# riffle-proto-grove-1_2.net
KiCad netlist of a schematic drawn in EAGLE
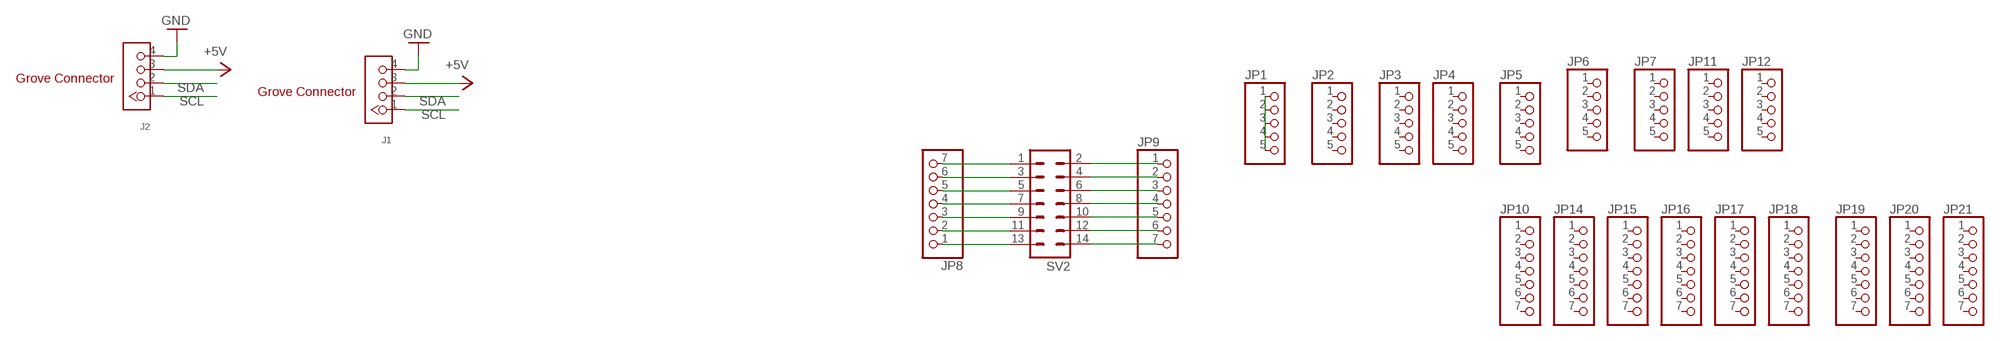
[diagram p0: schematic, sheet 1]

(export (version "E")
  (design (tool "Eeschema 10.0.6"))
  (components
    (comp (ref "J1")
      (value "TWIG-4P-2.0-2.0")
      (footprint "eagle-import:4P-2.0")
      (libsource (lib "eagle-import") (part "TWIG-4P-2.0-2.0"))
    )
    (comp (ref "J2")
      (value "TWIG-4P-2.0-2.0")
      (footprint "eagle-import:4P-2.0")
      (libsource (lib "eagle-import") (part "TWIG-4P-2.0-2.0"))
    )
    (comp (ref "JP1")
      (value "HEADER-1X570MIL")
      (footprint "eagle-import:1X05_ROUND_70")
      (libsource (lib "eagle-import") (part "HEADER-1X570MIL"))
    )
    (comp (ref "JP2")
      (value "HEADER-1X570MIL")
      (footprint "eagle-import:1X05_ROUND_70")
      (libsource (lib "eagle-import") (part "HEADER-1X570MIL"))
    )
    (comp (ref "JP3")
      (value "HEADER-1X570MIL")
      (footprint "eagle-import:1X05_ROUND_70")
      (libsource (lib "eagle-import") (part "HEADER-1X570MIL"))
    )
    (comp (ref "JP4")
      (value "HEADER-1X570MIL")
      (footprint "eagle-import:1X05_ROUND_70")
      (libsource (lib "eagle-import") (part "HEADER-1X570MIL"))
    )
    (comp (ref "JP5")
      (value "HEADER-1X570MIL")
      (footprint "eagle-import:1X05_ROUND_70")
      (libsource (lib "eagle-import") (part "HEADER-1X570MIL"))
    )
    (comp (ref "JP6")
      (value "HEADER-1X570MIL")
      (footprint "eagle-import:1X05_ROUND_70")
      (libsource (lib "eagle-import") (part "HEADER-1X570MIL"))
    )
    (comp (ref "JP7")
      (value "HEADER-1X570MIL")
      (footprint "eagle-import:1X05_ROUND_70")
      (libsource (lib "eagle-import") (part "HEADER-1X570MIL"))
    )
    (comp (ref "JP8")
      (value "HEADER-1X770MIL")
      (footprint "eagle-import:1X07_ROUND_70")
      (libsource (lib "eagle-import") (part "HEADER-1X770MIL"))
    )
    (comp (ref "JP9")
      (value "HEADER-1X770MIL")
      (footprint "eagle-import:1X07_ROUND_70")
      (libsource (lib "eagle-import") (part "HEADER-1X770MIL"))
    )
    (comp (ref "JP10")
      (value "HEADER-1X770MIL")
      (footprint "eagle-import:1X07_ROUND_70")
      (libsource (lib "eagle-import") (part "HEADER-1X770MIL"))
    )
    (comp (ref "JP11")
      (value "HEADER-1X570MIL")
      (footprint "eagle-import:1X05_ROUND_70")
      (libsource (lib "eagle-import") (part "HEADER-1X570MIL"))
    )
    (comp (ref "JP12")
      (value "HEADER-1X570MIL")
      (footprint "eagle-import:1X05_ROUND_70")
      (libsource (lib "eagle-import") (part "HEADER-1X570MIL"))
    )
    (comp (ref "JP14")
      (value "HEADER-1X770MIL")
      (footprint "eagle-import:1X07_ROUND_70")
      (libsource (lib "eagle-import") (part "HEADER-1X770MIL"))
    )
    (comp (ref "JP15")
      (value "HEADER-1X770MIL")
      (footprint "eagle-import:1X07_ROUND_70")
      (libsource (lib "eagle-import") (part "HEADER-1X770MIL"))
    )
    (comp (ref "JP16")
      (value "HEADER-1X770MIL")
      (footprint "eagle-import:1X07_ROUND_70")
      (libsource (lib "eagle-import") (part "HEADER-1X770MIL"))
    )
    (comp (ref "JP17")
      (value "HEADER-1X770MIL")
      (footprint "eagle-import:1X07_ROUND_70")
      (libsource (lib "eagle-import") (part "HEADER-1X770MIL"))
    )
    (comp (ref "JP18")
      (value "HEADER-1X770MIL")
      (footprint "eagle-import:1X07_ROUND_70")
      (libsource (lib "eagle-import") (part "HEADER-1X770MIL"))
    )
    (comp (ref "JP19")
      (value "HEADER-1X770MIL")
      (footprint "eagle-import:1X07_ROUND_70")
      (libsource (lib "eagle-import") (part "HEADER-1X770MIL"))
    )
    (comp (ref "JP20")
      (value "HEADER-1X770MIL")
      (footprint "eagle-import:1X07_ROUND_70")
      (libsource (lib "eagle-import") (part "HEADER-1X770MIL"))
    )
    (comp (ref "JP21")
      (value "HEADER-1X770MIL")
      (footprint "eagle-import:1X07_ROUND_70")
      (libsource (lib "eagle-import") (part "HEADER-1X770MIL"))
    )
    (comp (ref "SV2")
      (value "MA07-2")
      (footprint "eagle-import:MA07-2")
      (libsource (lib "eagle-import") (part "MA07-2"))
    )
  )
  (nets
    (net (code "1") (name "+5V") (class "Default")
      (node (ref "J1") (pin "3") (pinfunction "3_3") (pintype "bidirectional"))
      (node (ref "J2") (pin "3") (pinfunction "3_3") (pintype "bidirectional"))
    )
    (net (code "2") (name "/SCL") (class "Default")
      (node (ref "J1") (pin "1") (pinfunction "1_1") (pintype "bidirectional"))
      (node (ref "J2") (pin "1") (pinfunction "1_1") (pintype "bidirectional"))
    )
    (net (code "3") (name "/SDA") (class "Default")
      (node (ref "J1") (pin "2") (pinfunction "2_2") (pintype "bidirectional"))
      (node (ref "J2") (pin "2") (pinfunction "2_2") (pintype "bidirectional"))
    )
    (net (code "4") (name "GND") (class "Default")
      (node (ref "J1") (pin "4") (pinfunction "4_4") (pintype "bidirectional"))
      (node (ref "J2") (pin "4") (pinfunction "4_4") (pintype "bidirectional"))
    )
    (net (code "5") (name "Net-(JP1-Pad1)") (class "Default")
      (node (ref "JP1") (pin "1") (pinfunction "1_1") (pintype "passive"))
      (node (ref "JP1") (pin "2") (pinfunction "2_2") (pintype "passive"))
      (node (ref "JP1") (pin "3") (pinfunction "3_3") (pintype "passive"))
      (node (ref "JP1") (pin "4") (pinfunction "4_4") (pintype "passive"))
      (node (ref "JP1") (pin "5") (pinfunction "5_5") (pintype "passive"))
    )
    (net (code "6") (name "Net-(JP8-Pad1)") (class "Default")
      (node (ref "JP8") (pin "1") (pinfunction "1_1") (pintype "passive"))
      (node (ref "SV2") (pin "13") (pinfunction "13_13") (pintype "passive"))
    )
    (net (code "7") (name "Net-(JP8-Pad2)") (class "Default")
      (node (ref "JP8") (pin "2") (pinfunction "2_2") (pintype "passive"))
      (node (ref "SV2") (pin "11") (pinfunction "11_11") (pintype "passive"))
    )
    (net (code "8") (name "Net-(JP8-Pad3)") (class "Default")
      (node (ref "JP8") (pin "3") (pinfunction "3_3") (pintype "passive"))
      (node (ref "SV2") (pin "9") (pinfunction "9_9") (pintype "passive"))
    )
    (net (code "9") (name "Net-(JP8-Pad4)") (class "Default")
      (node (ref "JP8") (pin "4") (pinfunction "4_4") (pintype "passive"))
      (node (ref "SV2") (pin "7") (pinfunction "7_7") (pintype "passive"))
    )
    (net (code "10") (name "Net-(JP8-Pad5)") (class "Default")
      (node (ref "JP8") (pin "5") (pinfunction "5_5") (pintype "passive"))
      (node (ref "SV2") (pin "5") (pinfunction "5_5") (pintype "passive"))
    )
    (net (code "11") (name "Net-(JP8-Pad6)") (class "Default")
      (node (ref "JP8") (pin "6") (pinfunction "6_6") (pintype "passive"))
      (node (ref "SV2") (pin "3") (pinfunction "3_3") (pintype "passive"))
    )
    (net (code "12") (name "Net-(JP8-Pad7)") (class "Default")
      (node (ref "JP8") (pin "7") (pinfunction "7_7") (pintype "passive"))
      (node (ref "SV2") (pin "1") (pinfunction "1_1") (pintype "passive"))
    )
    (net (code "13") (name "Net-(JP9-Pad1)") (class "Default")
      (node (ref "JP9") (pin "1") (pinfunction "1_1") (pintype "passive"))
      (node (ref "SV2") (pin "2") (pinfunction "2_2") (pintype "passive"))
    )
    (net (code "14") (name "Net-(JP9-Pad2)") (class "Default")
      (node (ref "JP9") (pin "2") (pinfunction "2_2") (pintype "passive"))
      (node (ref "SV2") (pin "4") (pinfunction "4_4") (pintype "passive"))
    )
    (net (code "15") (name "Net-(JP9-Pad3)") (class "Default")
      (node (ref "JP9") (pin "3") (pinfunction "3_3") (pintype "passive"))
      (node (ref "SV2") (pin "6") (pinfunction "6_6") (pintype "passive"))
    )
    (net (code "16") (name "Net-(JP9-Pad4)") (class "Default")
      (node (ref "JP9") (pin "4") (pinfunction "4_4") (pintype "passive"))
      (node (ref "SV2") (pin "8") (pinfunction "8_8") (pintype "passive"))
    )
    (net (code "17") (name "Net-(JP9-Pad5)") (class "Default")
      (node (ref "JP9") (pin "5") (pinfunction "5_5") (pintype "passive"))
      (node (ref "SV2") (pin "10") (pinfunction "10_10") (pintype "passive"))
    )
    (net (code "18") (name "Net-(JP9-Pad6)") (class "Default")
      (node (ref "JP9") (pin "6") (pinfunction "6_6") (pintype "passive"))
      (node (ref "SV2") (pin "12") (pinfunction "12_12") (pintype "passive"))
    )
    (net (code "19") (name "Net-(JP9-Pad7)") (class "Default")
      (node (ref "JP9") (pin "7") (pinfunction "7_7") (pintype "passive"))
      (node (ref "SV2") (pin "14") (pinfunction "14_14") (pintype "passive"))
    )
    (net (code "20") (name "unconnected-(JP2-Pad1)") (class "Default")
      (node (ref "JP2") (pin "1") (pinfunction "1_1") (pintype "passive"))
    )
    (net (code "21") (name "unconnected-(JP2-Pad2)") (class "Default")
      (node (ref "JP2") (pin "2") (pinfunction "2_2") (pintype "passive"))
    )
    (net (code "22") (name "unconnected-(JP2-Pad3)") (class "Default")
      (node (ref "JP2") (pin "3") (pinfunction "3_3") (pintype "passive"))
    )
    (net (code "23") (name "unconnected-(JP2-Pad4)") (class "Default")
      (node (ref "JP2") (pin "4") (pinfunction "4_4") (pintype "passive"))
    )
    (net (code "24") (name "unconnected-(JP2-Pad5)") (class "Default")
      (node (ref "JP2") (pin "5") (pinfunction "5_5") (pintype "passive"))
    )
    (net (code "25") (name "unconnected-(JP3-Pad1)") (class "Default")
      (node (ref "JP3") (pin "1") (pinfunction "1_1") (pintype "passive"))
    )
    (net (code "26") (name "unconnected-(JP3-Pad2)") (class "Default")
      (node (ref "JP3") (pin "2") (pinfunction "2_2") (pintype "passive"))
    )
    (net (code "27") (name "unconnected-(JP3-Pad3)") (class "Default")
      (node (ref "JP3") (pin "3") (pinfunction "3_3") (pintype "passive"))
    )
    (net (code "28") (name "unconnected-(JP3-Pad4)") (class "Default")
      (node (ref "JP3") (pin "4") (pinfunction "4_4") (pintype "passive"))
    )
    (net (code "29") (name "unconnected-(JP3-Pad5)") (class "Default")
      (node (ref "JP3") (pin "5") (pinfunction "5_5") (pintype "passive"))
    )
    (net (code "30") (name "unconnected-(JP4-Pad1)") (class "Default")
      (node (ref "JP4") (pin "1") (pinfunction "1_1") (pintype "passive"))
    )
    (net (code "31") (name "unconnected-(JP4-Pad2)") (class "Default")
      (node (ref "JP4") (pin "2") (pinfunction "2_2") (pintype "passive"))
    )
    (net (code "32") (name "unconnected-(JP4-Pad3)") (class "Default")
      (node (ref "JP4") (pin "3") (pinfunction "3_3") (pintype "passive"))
    )
    (net (code "33") (name "unconnected-(JP4-Pad4)") (class "Default")
      (node (ref "JP4") (pin "4") (pinfunction "4_4") (pintype "passive"))
    )
    (net (code "34") (name "unconnected-(JP4-Pad5)") (class "Default")
      (node (ref "JP4") (pin "5") (pinfunction "5_5") (pintype "passive"))
    )
    (net (code "35") (name "unconnected-(JP5-Pad1)") (class "Default")
      (node (ref "JP5") (pin "1") (pinfunction "1_1") (pintype "passive"))
    )
    (net (code "36") (name "unconnected-(JP5-Pad2)") (class "Default")
      (node (ref "JP5") (pin "2") (pinfunction "2_2") (pintype "passive"))
    )
    (net (code "37") (name "unconnected-(JP5-Pad3)") (class "Default")
      (node (ref "JP5") (pin "3") (pinfunction "3_3") (pintype "passive"))
    )
    (net (code "38") (name "unconnected-(JP5-Pad4)") (class "Default")
      (node (ref "JP5") (pin "4") (pinfunction "4_4") (pintype "passive"))
    )
    (net (code "39") (name "unconnected-(JP5-Pad5)") (class "Default")
      (node (ref "JP5") (pin "5") (pinfunction "5_5") (pintype "passive"))
    )
    (net (code "40") (name "unconnected-(JP6-Pad1)") (class "Default")
      (node (ref "JP6") (pin "1") (pinfunction "1_1") (pintype "passive"))
    )
    (net (code "41") (name "unconnected-(JP6-Pad2)") (class "Default")
      (node (ref "JP6") (pin "2") (pinfunction "2_2") (pintype "passive"))
    )
    (net (code "42") (name "unconnected-(JP6-Pad3)") (class "Default")
      (node (ref "JP6") (pin "3") (pinfunction "3_3") (pintype "passive"))
    )
    (net (code "43") (name "unconnected-(JP6-Pad4)") (class "Default")
      (node (ref "JP6") (pin "4") (pinfunction "4_4") (pintype "passive"))
    )
    (net (code "44") (name "unconnected-(JP6-Pad5)") (class "Default")
      (node (ref "JP6") (pin "5") (pinfunction "5_5") (pintype "passive"))
    )
    (net (code "45") (name "unconnected-(JP7-Pad1)") (class "Default")
      (node (ref "JP7") (pin "1") (pinfunction "1_1") (pintype "passive"))
    )
    (net (code "46") (name "unconnected-(JP7-Pad2)") (class "Default")
      (node (ref "JP7") (pin "2") (pinfunction "2_2") (pintype "passive"))
    )
    (net (code "47") (name "unconnected-(JP7-Pad3)") (class "Default")
      (node (ref "JP7") (pin "3") (pinfunction "3_3") (pintype "passive"))
    )
    (net (code "48") (name "unconnected-(JP7-Pad4)") (class "Default")
      (node (ref "JP7") (pin "4") (pinfunction "4_4") (pintype "passive"))
    )
    (net (code "49") (name "unconnected-(JP7-Pad5)") (class "Default")
      (node (ref "JP7") (pin "5") (pinfunction "5_5") (pintype "passive"))
    )
    (net (code "50") (name "unconnected-(JP10-Pad1)") (class "Default")
      (node (ref "JP10") (pin "1") (pinfunction "1_1") (pintype "passive"))
    )
    (net (code "51") (name "unconnected-(JP10-Pad2)") (class "Default")
      (node (ref "JP10") (pin "2") (pinfunction "2_2") (pintype "passive"))
    )
    (net (code "52") (name "unconnected-(JP10-Pad3)") (class "Default")
      (node (ref "JP10") (pin "3") (pinfunction "3_3") (pintype "passive"))
    )
    (net (code "53") (name "unconnected-(JP10-Pad4)") (class "Default")
      (node (ref "JP10") (pin "4") (pinfunction "4_4") (pintype "passive"))
    )
    (net (code "54") (name "unconnected-(JP10-Pad5)") (class "Default")
      (node (ref "JP10") (pin "5") (pinfunction "5_5") (pintype "passive"))
    )
    (net (code "55") (name "unconnected-(JP10-Pad6)") (class "Default")
      (node (ref "JP10") (pin "6") (pinfunction "6_6") (pintype "passive"))
    )
    (net (code "56") (name "unconnected-(JP10-Pad7)") (class "Default")
      (node (ref "JP10") (pin "7") (pinfunction "7_7") (pintype "passive"))
    )
    (net (code "57") (name "unconnected-(JP11-Pad1)") (class "Default")
      (node (ref "JP11") (pin "1") (pinfunction "1_1") (pintype "passive"))
    )
    (net (code "58") (name "unconnected-(JP11-Pad2)") (class "Default")
      (node (ref "JP11") (pin "2") (pinfunction "2_2") (pintype "passive"))
    )
    (net (code "59") (name "unconnected-(JP11-Pad3)") (class "Default")
      (node (ref "JP11") (pin "3") (pinfunction "3_3") (pintype "passive"))
    )
    (net (code "60") (name "unconnected-(JP11-Pad4)") (class "Default")
      (node (ref "JP11") (pin "4") (pinfunction "4_4") (pintype "passive"))
    )
    (net (code "61") (name "unconnected-(JP11-Pad5)") (class "Default")
      (node (ref "JP11") (pin "5") (pinfunction "5_5") (pintype "passive"))
    )
    (net (code "62") (name "unconnected-(JP12-Pad1)") (class "Default")
      (node (ref "JP12") (pin "1") (pinfunction "1_1") (pintype "passive"))
    )
    (net (code "63") (name "unconnected-(JP12-Pad2)") (class "Default")
      (node (ref "JP12") (pin "2") (pinfunction "2_2") (pintype "passive"))
    )
    (net (code "64") (name "unconnected-(JP12-Pad3)") (class "Default")
      (node (ref "JP12") (pin "3") (pinfunction "3_3") (pintype "passive"))
    )
    (net (code "65") (name "unconnected-(JP12-Pad4)") (class "Default")
      (node (ref "JP12") (pin "4") (pinfunction "4_4") (pintype "passive"))
    )
    (net (code "66") (name "unconnected-(JP12-Pad5)") (class "Default")
      (node (ref "JP12") (pin "5") (pinfunction "5_5") (pintype "passive"))
    )
    (net (code "67") (name "unconnected-(JP14-Pad1)") (class "Default")
      (node (ref "JP14") (pin "1") (pinfunction "1_1") (pintype "passive"))
    )
    (net (code "68") (name "unconnected-(JP14-Pad2)") (class "Default")
      (node (ref "JP14") (pin "2") (pinfunction "2_2") (pintype "passive"))
    )
    (net (code "69") (name "unconnected-(JP14-Pad3)") (class "Default")
      (node (ref "JP14") (pin "3") (pinfunction "3_3") (pintype "passive"))
    )
    (net (code "70") (name "unconnected-(JP14-Pad4)") (class "Default")
      (node (ref "JP14") (pin "4") (pinfunction "4_4") (pintype "passive"))
    )
    (net (code "71") (name "unconnected-(JP14-Pad5)") (class "Default")
      (node (ref "JP14") (pin "5") (pinfunction "5_5") (pintype "passive"))
    )
    (net (code "72") (name "unconnected-(JP14-Pad6)") (class "Default")
      (node (ref "JP14") (pin "6") (pinfunction "6_6") (pintype "passive"))
    )
    (net (code "73") (name "unconnected-(JP14-Pad7)") (class "Default")
      (node (ref "JP14") (pin "7") (pinfunction "7_7") (pintype "passive"))
    )
    (net (code "74") (name "unconnected-(JP15-Pad1)") (class "Default")
      (node (ref "JP15") (pin "1") (pinfunction "1_1") (pintype "passive"))
    )
    (net (code "75") (name "unconnected-(JP15-Pad2)") (class "Default")
      (node (ref "JP15") (pin "2") (pinfunction "2_2") (pintype "passive"))
    )
    (net (code "76") (name "unconnected-(JP15-Pad3)") (class "Default")
      (node (ref "JP15") (pin "3") (pinfunction "3_3") (pintype "passive"))
    )
    (net (code "77") (name "unconnected-(JP15-Pad4)") (class "Default")
      (node (ref "JP15") (pin "4") (pinfunction "4_4") (pintype "passive"))
    )
    (net (code "78") (name "unconnected-(JP15-Pad5)") (class "Default")
      (node (ref "JP15") (pin "5") (pinfunction "5_5") (pintype "passive"))
    )
    (net (code "79") (name "unconnected-(JP15-Pad6)") (class "Default")
      (node (ref "JP15") (pin "6") (pinfunction "6_6") (pintype "passive"))
    )
    (net (code "80") (name "unconnected-(JP15-Pad7)") (class "Default")
      (node (ref "JP15") (pin "7") (pinfunction "7_7") (pintype "passive"))
    )
    (net (code "81") (name "unconnected-(JP16-Pad1)") (class "Default")
      (node (ref "JP16") (pin "1") (pinfunction "1_1") (pintype "passive"))
    )
    (net (code "82") (name "unconnected-(JP16-Pad2)") (class "Default")
      (node (ref "JP16") (pin "2") (pinfunction "2_2") (pintype "passive"))
    )
    (net (code "83") (name "unconnected-(JP16-Pad3)") (class "Default")
      (node (ref "JP16") (pin "3") (pinfunction "3_3") (pintype "passive"))
    )
    (net (code "84") (name "unconnected-(JP16-Pad4)") (class "Default")
      (node (ref "JP16") (pin "4") (pinfunction "4_4") (pintype "passive"))
    )
    (net (code "85") (name "unconnected-(JP16-Pad5)") (class "Default")
      (node (ref "JP16") (pin "5") (pinfunction "5_5") (pintype "passive"))
    )
    (net (code "86") (name "unconnected-(JP16-Pad6)") (class "Default")
      (node (ref "JP16") (pin "6") (pinfunction "6_6") (pintype "passive"))
    )
    (net (code "87") (name "unconnected-(JP16-Pad7)") (class "Default")
      (node (ref "JP16") (pin "7") (pinfunction "7_7") (pintype "passive"))
    )
    (net (code "88") (name "unconnected-(JP17-Pad1)") (class "Default")
      (node (ref "JP17") (pin "1") (pinfunction "1_1") (pintype "passive"))
    )
    (net (code "89") (name "unconnected-(JP17-Pad2)") (class "Default")
      (node (ref "JP17") (pin "2") (pinfunction "2_2") (pintype "passive"))
    )
    (net (code "90") (name "unconnected-(JP17-Pad3)") (class "Default")
      (node (ref "JP17") (pin "3") (pinfunction "3_3") (pintype "passive"))
    )
    (net (code "91") (name "unconnected-(JP17-Pad4)") (class "Default")
      (node (ref "JP17") (pin "4") (pinfunction "4_4") (pintype "passive"))
    )
    (net (code "92") (name "unconnected-(JP17-Pad5)") (class "Default")
      (node (ref "JP17") (pin "5") (pinfunction "5_5") (pintype "passive"))
    )
    (net (code "93") (name "unconnected-(JP17-Pad6)") (class "Default")
      (node (ref "JP17") (pin "6") (pinfunction "6_6") (pintype "passive"))
    )
    (net (code "94") (name "unconnected-(JP17-Pad7)") (class "Default")
      (node (ref "JP17") (pin "7") (pinfunction "7_7") (pintype "passive"))
    )
    (net (code "95") (name "unconnected-(JP18-Pad1)") (class "Default")
      (node (ref "JP18") (pin "1") (pinfunction "1_1") (pintype "passive"))
    )
    (net (code "96") (name "unconnected-(JP18-Pad2)") (class "Default")
      (node (ref "JP18") (pin "2") (pinfunction "2_2") (pintype "passive"))
    )
    (net (code "97") (name "unconnected-(JP18-Pad3)") (class "Default")
      (node (ref "JP18") (pin "3") (pinfunction "3_3") (pintype "passive"))
    )
    (net (code "98") (name "unconnected-(JP18-Pad4)") (class "Default")
      (node (ref "JP18") (pin "4") (pinfunction "4_4") (pintype "passive"))
    )
    (net (code "99") (name "unconnected-(JP18-Pad5)") (class "Default")
      (node (ref "JP18") (pin "5") (pinfunction "5_5") (pintype "passive"))
    )
    (net (code "100") (name "unconnected-(JP18-Pad6)") (class "Default")
      (node (ref "JP18") (pin "6") (pinfunction "6_6") (pintype "passive"))
    )
    (net (code "101") (name "unconnected-(JP18-Pad7)") (class "Default")
      (node (ref "JP18") (pin "7") (pinfunction "7_7") (pintype "passive"))
    )
    (net (code "102") (name "unconnected-(JP19-Pad1)") (class "Default")
      (node (ref "JP19") (pin "1") (pinfunction "1_1") (pintype "passive"))
    )
    (net (code "103") (name "unconnected-(JP19-Pad2)") (class "Default")
      (node (ref "JP19") (pin "2") (pinfunction "2_2") (pintype "passive"))
    )
    (net (code "104") (name "unconnected-(JP19-Pad3)") (class "Default")
      (node (ref "JP19") (pin "3") (pinfunction "3_3") (pintype "passive"))
    )
    (net (code "105") (name "unconnected-(JP19-Pad4)") (class "Default")
      (node (ref "JP19") (pin "4") (pinfunction "4_4") (pintype "passive"))
    )
    (net (code "106") (name "unconnected-(JP19-Pad5)") (class "Default")
      (node (ref "JP19") (pin "5") (pinfunction "5_5") (pintype "passive"))
    )
    (net (code "107") (name "unconnected-(JP19-Pad6)") (class "Default")
      (node (ref "JP19") (pin "6") (pinfunction "6_6") (pintype "passive"))
    )
    (net (code "108") (name "unconnected-(JP19-Pad7)") (class "Default")
      (node (ref "JP19") (pin "7") (pinfunction "7_7") (pintype "passive"))
    )
    (net (code "109") (name "unconnected-(JP20-Pad1)") (class "Default")
      (node (ref "JP20") (pin "1") (pinfunction "1_1") (pintype "passive"))
    )
    (net (code "110") (name "unconnected-(JP20-Pad2)") (class "Default")
      (node (ref "JP20") (pin "2") (pinfunction "2_2") (pintype "passive"))
    )
    (net (code "111") (name "unconnected-(JP20-Pad3)") (class "Default")
      (node (ref "JP20") (pin "3") (pinfunction "3_3") (pintype "passive"))
    )
    (net (code "112") (name "unconnected-(JP20-Pad4)") (class "Default")
      (node (ref "JP20") (pin "4") (pinfunction "4_4") (pintype "passive"))
    )
    (net (code "113") (name "unconnected-(JP20-Pad5)") (class "Default")
      (node (ref "JP20") (pin "5") (pinfunction "5_5") (pintype "passive"))
    )
    (net (code "114") (name "unconnected-(JP20-Pad6)") (class "Default")
      (node (ref "JP20") (pin "6") (pinfunction "6_6") (pintype "passive"))
    )
    (net (code "115") (name "unconnected-(JP20-Pad7)") (class "Default")
      (node (ref "JP20") (pin "7") (pinfunction "7_7") (pintype "passive"))
    )
    (net (code "116") (name "unconnected-(JP21-Pad1)") (class "Default")
      (node (ref "JP21") (pin "1") (pinfunction "1_1") (pintype "passive"))
    )
    (net (code "117") (name "unconnected-(JP21-Pad2)") (class "Default")
      (node (ref "JP21") (pin "2") (pinfunction "2_2") (pintype "passive"))
    )
    (net (code "118") (name "unconnected-(JP21-Pad3)") (class "Default")
      (node (ref "JP21") (pin "3") (pinfunction "3_3") (pintype "passive"))
    )
    (net (code "119") (name "unconnected-(JP21-Pad4)") (class "Default")
      (node (ref "JP21") (pin "4") (pinfunction "4_4") (pintype "passive"))
    )
    (net (code "120") (name "unconnected-(JP21-Pad5)") (class "Default")
      (node (ref "JP21") (pin "5") (pinfunction "5_5") (pintype "passive"))
    )
    (net (code "121") (name "unconnected-(JP21-Pad6)") (class "Default")
      (node (ref "JP21") (pin "6") (pinfunction "6_6") (pintype "passive"))
    )
    (net (code "122") (name "unconnected-(JP21-Pad7)") (class "Default")
      (node (ref "JP21") (pin "7") (pinfunction "7_7") (pintype "passive"))
    )
  )
)
